# extBoard_sheet3_interrupt_generator.net
KiCad netlist of a schematic drawn in Altium Designer
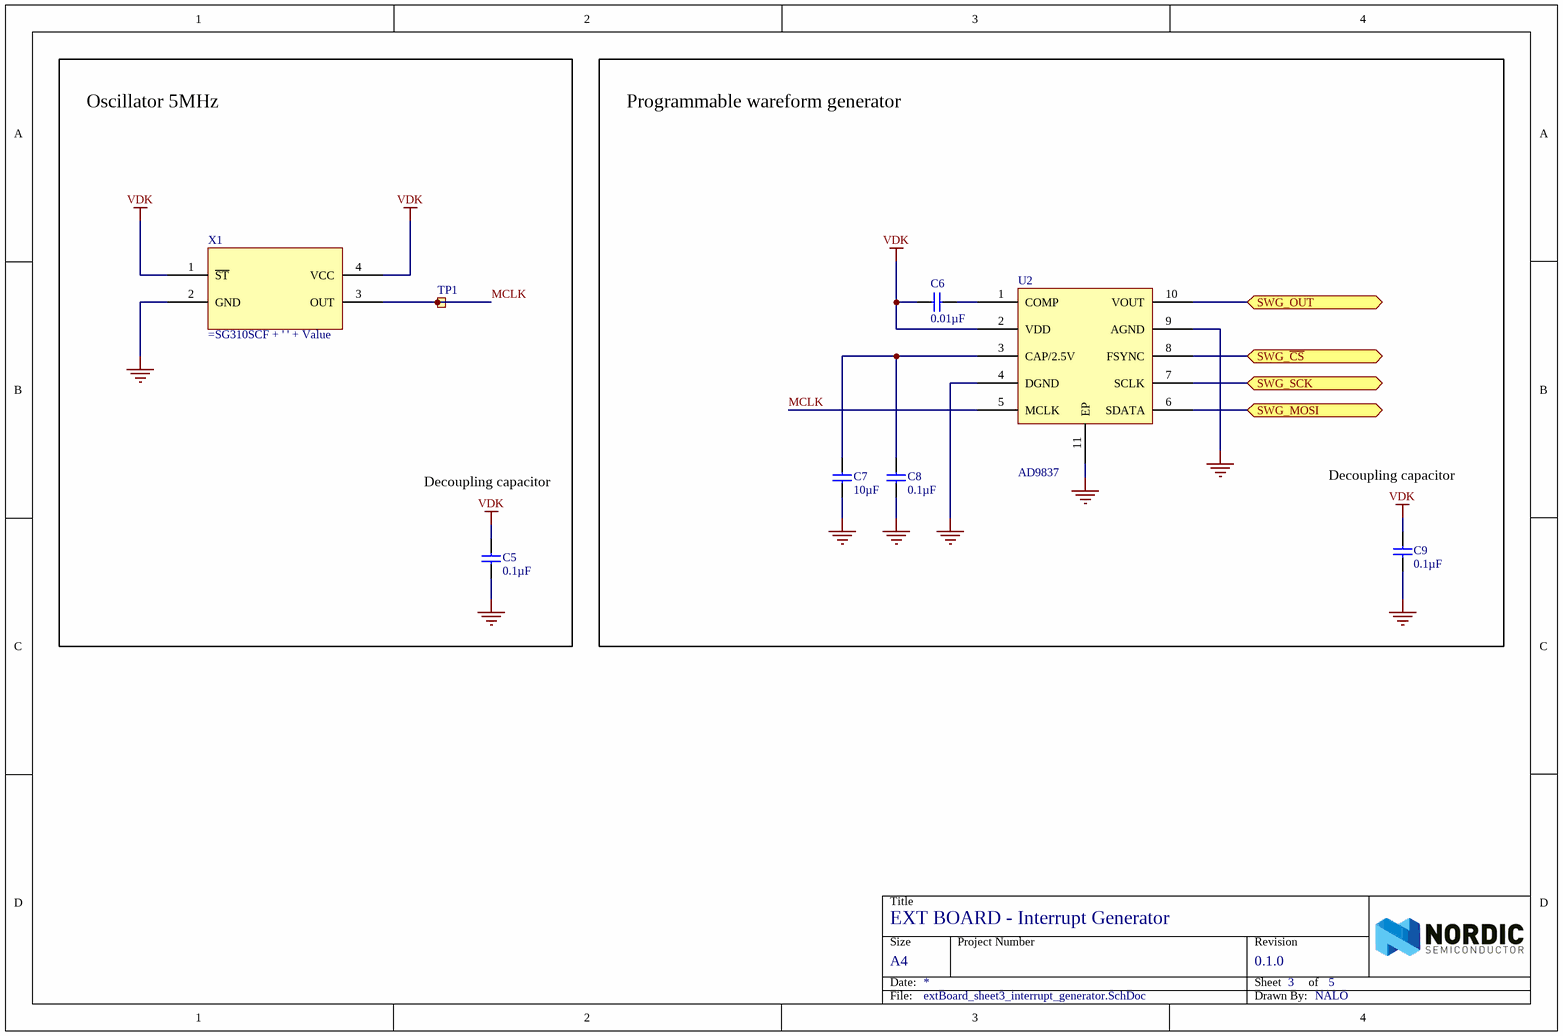
[diagram p0: extBoard_sheet3_interrupt_generator.SchDoc]

(export (version "E")
  (design (tool "Eeschema 10.0.6"))
  (components
    (comp (ref "C5")
      (value "0.1µF")
      (footprint "CAPC2012X11L")
      (description "Capacitor, X5R, ±10%")
      (fields (field (name "PART NUMBER") "C0805-4µ7") (field (name "PUBLISHER") "Nordic Semiconductor"))
      (libsource (lib "pca10056") (part "CAP_0805"))
    )
    (comp (ref "C6")
      (value "0.01µF")
      (footprint "CAPC2012X11L")
      (description "Capacitor, X5R, ±10%")
      (fields (field (name "PART NUMBER") "C0805-4µ7") (field (name "PUBLISHER") "Nordic Semiconductor"))
      (libsource (lib "pca10056") (part "CAP_0805"))
    )
    (comp (ref "C7")
      (value "10µF")
      (footprint "CAPC2012X11L")
      (description "Capacitor, X5R, ±10%")
      (fields (field (name "PART NUMBER") "C0805-4µ7") (field (name "PUBLISHER") "Nordic Semiconductor"))
      (libsource (lib "pca10056") (part "CAP_0805"))
    )
    (comp (ref "C8")
      (value "0.1µF")
      (footprint "CAPC2012X11L")
      (description "Capacitor, X5R, ±10%")
      (fields (field (name "PART NUMBER") "C0805-4µ7") (field (name "PUBLISHER") "Nordic Semiconductor"))
      (libsource (lib "pca10056") (part "CAP_0805"))
    )
    (comp (ref "C9")
      (value "0.1µF")
      (footprint "CAPC2012X11L")
      (description "Capacitor, X5R, ±10%")
      (fields (field (name "PART NUMBER") "C0805-4µ7") (field (name "PUBLISHER") "Nordic Semiconductor"))
      (libsource (lib "pca10056") (part "CAP_0805"))
    )
    (comp (ref "TP1")
      (value "TP")
      (footprint "TESTPAD-TH")
      (description "Testpoint, through hole")
      (fields (field (name "PART NUMBER") "Testpoint TH") (field (name "PUBLISHER") "Nordic Semiconductor"))
      (libsource (lib "pca10056") (part "Testpoint TH"))
    )
    (comp (ref "U2")
      (value "AD9837")
      (footprint "DFN50P300X300X95-10N")
      (libsource (lib "extBoardLib") (part "AD9837"))
    )
    (comp (ref "X1") (value "16MHz") (footprint "SG310SCF") (libsource (lib "extBoardLib") (part "SG310SCF")))
  )
  (nets
    (net (code "1") (name "/MCLK") (class "Default")
      (node (ref "TP1") (pin "1") (pinfunction "1_1") (pintype "passive"))
      (node (ref "U2") (pin "5") (pinfunction "MCLK_5") (pintype "passive"))
      (node (ref "X1") (pin "3") (pinfunction "OUT_3") (pintype "passive"))
    )
    (net (code "2") (name "/SWG_MOSI") (class "Default")
      (node (ref "U2") (pin "6") (pinfunction "SDATA_6") (pintype "passive"))
    )
    (net (code "3") (name "/SWG_OUT") (class "Default")
      (node (ref "U2") (pin "10") (pinfunction "VOUT_10") (pintype "passive"))
    )
    (net (code "4") (name "/SWG_SCK") (class "Default")
      (node (ref "U2") (pin "7") (pinfunction "SCLK_7") (pintype "passive"))
    )
    (net (code "5") (name "/SWG_~{CS}") (class "Default")
      (node (ref "U2") (pin "8") (pinfunction "FSYNC_8") (pintype "passive"))
    )
    (net (code "6") (name "GND") (class "Default")
      (node (ref "C5") (pin "1") (pinfunction "1_1") (pintype "passive"))
      (node (ref "C7") (pin "1") (pinfunction "1_1") (pintype "passive"))
      (node (ref "C8") (pin "1") (pinfunction "1_1") (pintype "passive"))
      (node (ref "C9") (pin "1") (pinfunction "1_1") (pintype "passive"))
      (node (ref "U2") (pin "11") (pinfunction "EP_11") (pintype "passive"))
      (node (ref "U2") (pin "4") (pinfunction "DGND_4") (pintype "passive"))
      (node (ref "U2") (pin "9") (pinfunction "AGND_9") (pintype "passive"))
      (node (ref "X1") (pin "2") (pinfunction "GND_2") (pintype "passive"))
    )
    (net (code "7") (name "Net-(U2-CAP{slash}2.5V)") (class "Default")
      (node (ref "C7") (pin "2") (pinfunction "2_2") (pintype "passive"))
      (node (ref "C8") (pin "2") (pinfunction "2_2") (pintype "passive"))
      (node (ref "U2") (pin "3") (pinfunction "CAP/2.5V_3") (pintype "passive"))
    )
    (net (code "8") (name "Net-(U2-COMP)") (class "Default")
      (node (ref "C6") (pin "1") (pinfunction "1_1") (pintype "passive"))
      (node (ref "U2") (pin "1") (pinfunction "COMP_1") (pintype "passive"))
    )
    (net (code "9") (name "VDK") (class "Default")
      (node (ref "C5") (pin "2") (pinfunction "2_2") (pintype "passive"))
      (node (ref "C6") (pin "2") (pinfunction "2_2") (pintype "passive"))
      (node (ref "C9") (pin "2") (pinfunction "2_2") (pintype "passive"))
      (node (ref "U2") (pin "2") (pinfunction "VDD_2") (pintype "passive"))
      (node (ref "X1") (pin "1") (pinfunction "~{ST}_1") (pintype "passive"))
      (node (ref "X1") (pin "4") (pinfunction "VCC_4") (pintype "passive"))
    )
  )
)
